# RelayBoard_for_M15F.net
KiCad netlist of a schematic drawn in EAGLE
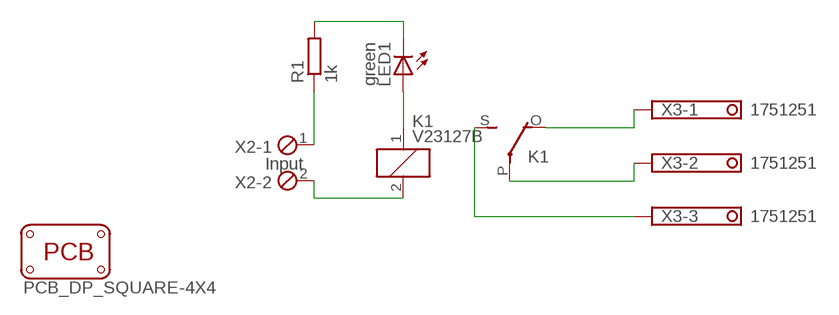
[diagram p0: schematic, sheet 1]

(export (version "E")
  (design (tool "Eeschema 10.0.6"))
  (components
    (comp (ref "K1")
      (value "V23127B")
      (footprint "eagle-import:V23127B")
      (libsource (lib "eagle-import") (part "V23127B"))
    )
    (comp (ref "LED1")
      (value "green")
      (footprint "eagle-import:LED-805")
      (libsource (lib "eagle-import") (part "LED-0805"))
    )
    (comp (ref "PCB1")
      (value "PCB_DP_SQUARE-4X4")
      (footprint "eagle-import:DP4040_V1")
      (libsource (lib "eagle-import") (part "PCB_DP_SQUARE-4X4"))
    )
    (comp (ref "R1")
      (value "1k")
      (footprint "eagle-import:R805")
      (libsource (lib "eagle-import") (part "RESISTOR-0805R805"))
    )
    (comp (ref "X2")
      (value "Input")
      (footprint "eagle-import:2POL254")
      (libsource (lib "eagle-import") (part "MPT2"))
    )
    (comp (ref "X3")
      (value "1751251")
      (footprint "eagle-import:1751251")
      (libsource (lib "eagle-import") (part "1751251"))
    )
  )
  (nets
    (net (code "1") (name "Net-(K1-Pad1)") (class "Default")
      (node (ref "K1") (pin "1") (pinfunction "1_1") (pintype "passive"))
      (node (ref "LED1") (pin "A") (pinfunction "A_A") (pintype "passive"))
    )
    (net (code "2") (name "Net-(LED1-PadC)") (class "Default")
      (node (ref "LED1") (pin "C") (pinfunction "C_C") (pintype "passive"))
      (node (ref "R1") (pin "2") (pinfunction "2_2") (pintype "passive"))
    )
    (net (code "3") (name "Net-(R1-Pad1)") (class "Default")
      (node (ref "R1") (pin "1") (pinfunction "1_1") (pintype "passive"))
      (node (ref "X2") (pin "1") (pinfunction "1_1") (pintype "passive"))
    )
    (net (code "4") (name "Net-(X2B-1)") (class "Default")
      (node (ref "K1") (pin "2") (pinfunction "2_2") (pintype "passive"))
      (node (ref "X2") (pin "2") (pinfunction "1_2") (pintype "passive"))
    )
    (net (code "5") (name "Net-(X3A-K)") (class "Default")
      (node (ref "K1") (pin "O") (pinfunction "O_O") (pintype "passive"))
      (node (ref "X3") (pin "1") (pinfunction "K_1") (pintype "passive"))
    )
    (net (code "6") (name "Net-(X3B-K)") (class "Default")
      (node (ref "K1") (pin "P") (pinfunction "P_P") (pintype "passive"))
      (node (ref "X3") (pin "2") (pinfunction "K_2") (pintype "passive"))
    )
    (net (code "7") (name "Net-(X3C-K)") (class "Default")
      (node (ref "K1") (pin "S") (pinfunction "S_S") (pintype "passive"))
      (node (ref "X3") (pin "3") (pinfunction "K_3") (pintype "passive"))
    )
  )
)
